# schematic.net
KiCad netlist of a schematic drawn in Altium Designer
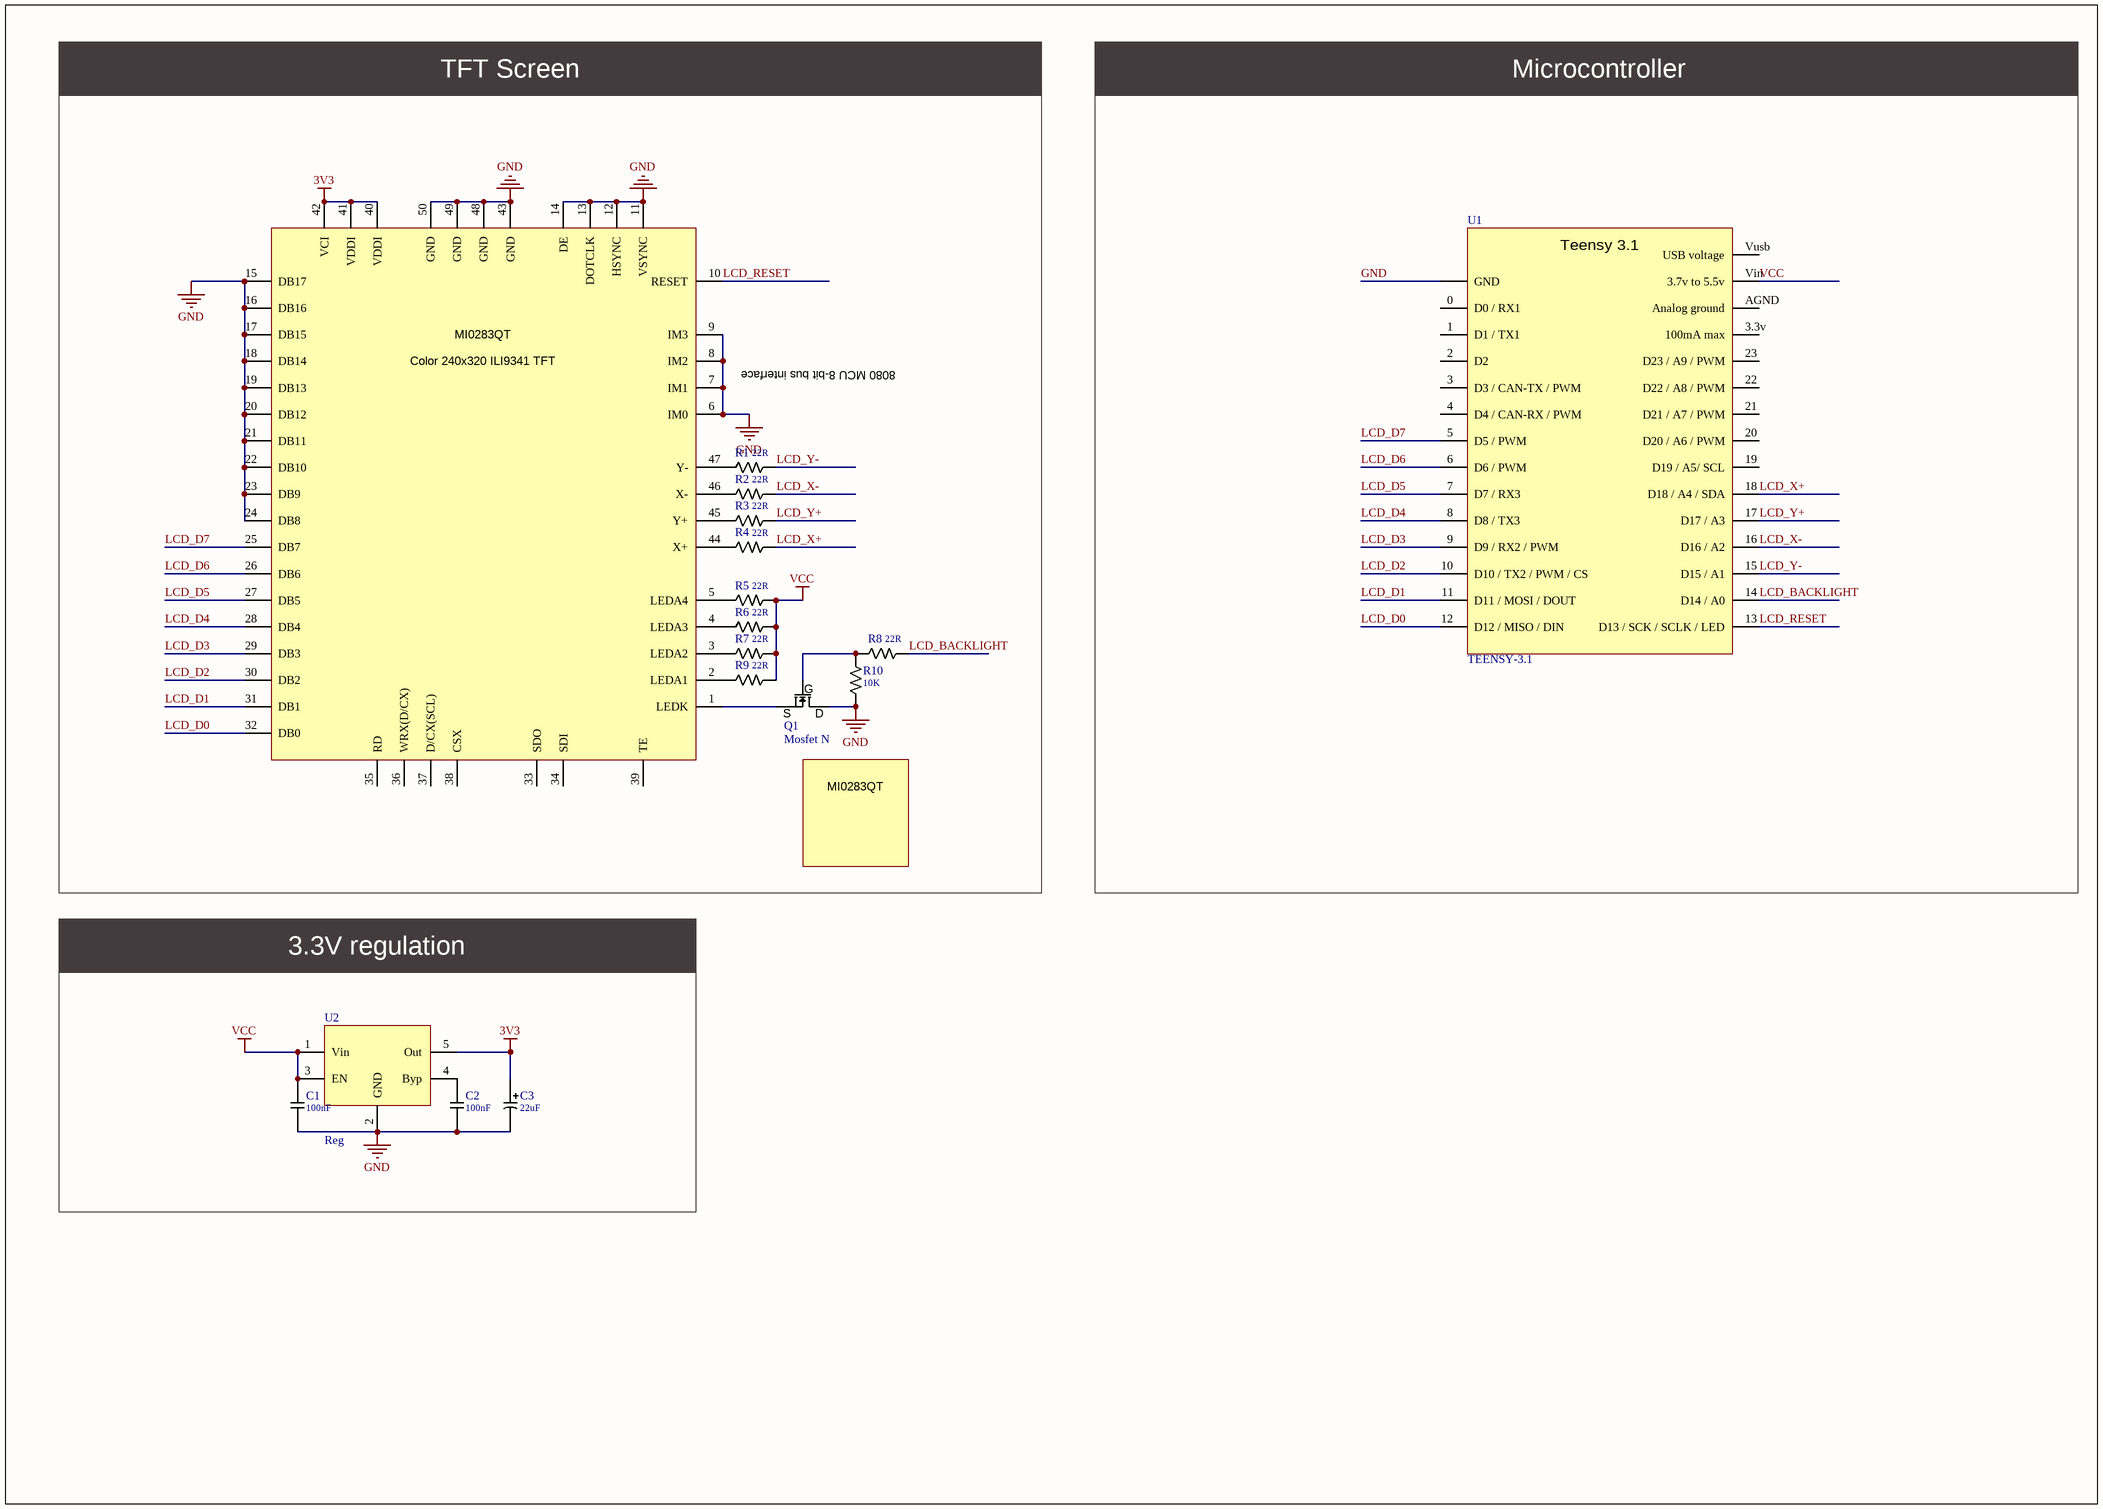
[diagram p0: schematic.SchDoc]

(export (version "E")
  (design (tool "Eeschema 10.0.6"))
  (components
    (comp (ref "C1")
      (value "100nF")
      (footprint "CAP-0603-GEN")
      (description "Capacitor")
      (fields (field (name "Comment") "CAPACITOR"))
      (libsource (lib "custom") (part "CAPACITOR"))
    )
    (comp (ref "C2")
      (value "100nF")
      (footprint "CAP-0603-GEN")
      (description "Capacitor")
      (fields (field (name "Comment") "CAPACITOR"))
      (libsource (lib "custom") (part "CAPACITOR"))
    )
    (comp (ref "C3")
      (value "22uF")
      (footprint "CAP-0603-POL")
      (description "Polarized capacitor")
      (fields (field (name "Comment") "CAPACITOR-POLARIZED"))
      (libsource (lib "custom") (part "CAPACITOR-POLARIZED"))
    )
    (comp (ref "Q1")
      (value "Mosfet N")
      (footprint "SOT23-3")
      (description "N-channel mosfet")
      (libsource (lib "custom") (part "MOSFET-N"))
    )
    (comp (ref "R1")
      (value "22R")
      (footprint "RESISTOR-0603")
      (description "Resistor")
      (fields (field (name "Comment") "RESISTOR"))
      (libsource (lib "custom") (part "RESISTOR"))
    )
    (comp (ref "R2")
      (value "22R")
      (footprint "RESISTOR-0603")
      (description "Resistor")
      (fields (field (name "Comment") "RESISTOR"))
      (libsource (lib "custom") (part "RESISTOR"))
    )
    (comp (ref "R3")
      (value "22R")
      (footprint "RESISTOR-0603")
      (description "Resistor")
      (fields (field (name "Comment") "RESISTOR"))
      (libsource (lib "custom") (part "RESISTOR"))
    )
    (comp (ref "R4")
      (value "22R")
      (footprint "RESISTOR-0603")
      (description "Resistor")
      (fields (field (name "Comment") "RESISTOR"))
      (libsource (lib "custom") (part "RESISTOR"))
    )
    (comp (ref "R5")
      (value "22R")
      (footprint "RESISTOR-0603")
      (description "Resistor")
      (fields (field (name "Comment") "RESISTOR"))
      (libsource (lib "custom") (part "RESISTOR"))
    )
    (comp (ref "R6")
      (value "22R")
      (footprint "RESISTOR-0603")
      (description "Resistor")
      (fields (field (name "Comment") "RESISTOR"))
      (libsource (lib "custom") (part "RESISTOR"))
    )
    (comp (ref "R7")
      (value "22R")
      (footprint "RESISTOR-0603")
      (description "Resistor")
      (fields (field (name "Comment") "RESISTOR"))
      (libsource (lib "custom") (part "RESISTOR"))
    )
    (comp (ref "R8")
      (value "22R")
      (footprint "RESISTOR-0603")
      (description "Resistor")
      (fields (field (name "Comment") "RESISTOR"))
      (libsource (lib "custom") (part "RESISTOR"))
    )
    (comp (ref "R9")
      (value "22R")
      (footprint "RESISTOR-0603")
      (description "Resistor")
      (fields (field (name "Comment") "RESISTOR"))
      (libsource (lib "custom") (part "RESISTOR"))
    )
    (comp (ref "R10")
      (value "10K")
      (footprint "RESISTOR-0603")
      (description "Resistor")
      (libsource (lib "custom") (part "RESISTOR"))
    )
    (comp (ref "TFT1")
      (value "TFT")
      (footprint "FCI-62684-50210E9ALF")
      (description "MI0283QT 2.8\" TFT")
      (libsource (lib "custom") (part "MI0283QT-11"))
    )
    (comp (ref "TFT2")
      (value "Screen")
      (footprint "MI0283QT")
      (description "MI0283QT TFT screen")
      (libsource (lib "custom") (part "MI0283QT"))
    )
    (comp (ref "U1")
      (value "TEENSY-3.1")
      (footprint "TEENSY-3.1")
      (description "Teensy 3.1 breakout")
      (libsource (lib "custom") (part "TEENSY-3.1"))
    )
    (comp (ref "U2")
      (value "Reg")
      (footprint "SOT23-5")
      (description "Voltage regulator")
      (libsource (lib "custom") (part "SOT23-REG"))
    )
  )
  (nets
    (net (code "1") (name "/LCD_BACKLIGHT") (class "Default")
      (node (ref "R8") (pin "2") (pinfunction "2_2") (pintype "passive"))
      (node (ref "U1") (pin "14") (pinfunction "D14_/_A0_14") (pintype "passive"))
    )
    (net (code "2") (name "/LCD_D0") (class "Default")
      (node (ref "TFT1") (pin "32") (pinfunction "DB0_32") (pintype "passive"))
      (node (ref "U1") (pin "12") (pinfunction "D12_/_MISO_/_DIN_12") (pintype "passive"))
    )
    (net (code "3") (name "/LCD_D1") (class "Default")
      (node (ref "TFT1") (pin "31") (pinfunction "DB1_31") (pintype "passive"))
      (node (ref "U1") (pin "11") (pinfunction "D11_/_MOSI_/_DOUT_11") (pintype "passive"))
    )
    (net (code "4") (name "/LCD_D2") (class "Default")
      (node (ref "TFT1") (pin "30") (pinfunction "DB2_30") (pintype "passive"))
      (node (ref "U1") (pin "10") (pinfunction "D10_/_TX2_/_PWM_/_CS_10") (pintype "passive"))
    )
    (net (code "5") (name "/LCD_D3") (class "Default")
      (node (ref "TFT1") (pin "29") (pinfunction "DB3_29") (pintype "passive"))
      (node (ref "U1") (pin "9") (pinfunction "D9_/_RX2_/_PWM_9") (pintype "passive"))
    )
    (net (code "6") (name "/LCD_D4") (class "Default")
      (node (ref "TFT1") (pin "28") (pinfunction "DB4_28") (pintype "passive"))
      (node (ref "U1") (pin "8") (pinfunction "D8_/_TX3_8") (pintype "passive"))
    )
    (net (code "7") (name "/LCD_D5") (class "Default")
      (node (ref "TFT1") (pin "27") (pinfunction "DB5_27") (pintype "passive"))
      (node (ref "U1") (pin "7") (pinfunction "D7_/_RX3_7") (pintype "passive"))
    )
    (net (code "8") (name "/LCD_D6") (class "Default")
      (node (ref "TFT1") (pin "26") (pinfunction "DB6_26") (pintype "passive"))
      (node (ref "U1") (pin "6") (pinfunction "D6_/_PWM_6") (pintype "passive"))
    )
    (net (code "9") (name "/LCD_D7") (class "Default")
      (node (ref "TFT1") (pin "25") (pinfunction "DB7_25") (pintype "passive"))
      (node (ref "U1") (pin "5") (pinfunction "D5_/_PWM_5") (pintype "passive"))
    )
    (net (code "10") (name "/LCD_RESET") (class "Default")
      (node (ref "TFT1") (pin "10") (pinfunction "RESET_10") (pintype "passive"))
      (node (ref "U1") (pin "13") (pinfunction "D13_/_SCK_/_SCLK_/_LED_13") (pintype "passive"))
    )
    (net (code "11") (name "/LCD_X+") (class "Default")
      (node (ref "R4") (pin "2") (pinfunction "2_2") (pintype "passive"))
      (node (ref "U1") (pin "18") (pinfunction "D18_/_A4_/_SDA_18") (pintype "passive"))
    )
    (net (code "12") (name "/LCD_X-") (class "Default")
      (node (ref "R2") (pin "2") (pinfunction "2_2") (pintype "passive"))
      (node (ref "U1") (pin "16") (pinfunction "D16_/_A2_16") (pintype "passive"))
    )
    (net (code "13") (name "/LCD_Y+") (class "Default")
      (node (ref "R3") (pin "2") (pinfunction "2_2") (pintype "passive"))
      (node (ref "U1") (pin "17") (pinfunction "D17_/_A3_17") (pintype "passive"))
    )
    (net (code "14") (name "/LCD_Y-") (class "Default")
      (node (ref "R1") (pin "2") (pinfunction "2_2") (pintype "passive"))
      (node (ref "U1") (pin "15") (pinfunction "D15_/_A1_15") (pintype "passive"))
    )
    (net (code "15") (name "3V3") (class "Default")
      (node (ref "C3") (pin "1") (pinfunction "1_1") (pintype "passive"))
      (node (ref "TFT1") (pin "40") (pinfunction "VDDI_40") (pintype "passive"))
      (node (ref "TFT1") (pin "41") (pinfunction "VDDI_41") (pintype "passive"))
      (node (ref "TFT1") (pin "42") (pinfunction "VCI_42") (pintype "passive"))
      (node (ref "U2") (pin "5") (pinfunction "Out_5") (pintype "passive"))
    )
    (net (code "16") (name "GND") (class "Default")
      (node (ref "C1") (pin "1") (pinfunction "1_1") (pintype "passive"))
      (node (ref "C2") (pin "1") (pinfunction "1_1") (pintype "passive"))
      (node (ref "C3") (pin "2") (pinfunction "2_2") (pintype "passive"))
      (node (ref "Q1") (pin "3") (pinfunction "Drain_3") (pintype "passive"))
      (node (ref "R10") (pin "2") (pinfunction "2_2") (pintype "passive"))
      (node (ref "TFT1") (pin "11") (pinfunction "VSYNC_11") (pintype "passive"))
      (node (ref "TFT1") (pin "12") (pinfunction "HSYNC_12") (pintype "passive"))
      (node (ref "TFT1") (pin "13") (pinfunction "DOTCLK_13") (pintype "passive"))
      (node (ref "TFT1") (pin "14") (pinfunction "DE_14") (pintype "passive"))
      (node (ref "TFT1") (pin "15") (pinfunction "DB17_15") (pintype "passive"))
      (node (ref "TFT1") (pin "16") (pinfunction "DB16_16") (pintype "passive"))
      (node (ref "TFT1") (pin "17") (pinfunction "DB15_17") (pintype "passive"))
      (node (ref "TFT1") (pin "18") (pinfunction "DB14_18") (pintype "passive"))
      (node (ref "TFT1") (pin "19") (pinfunction "DB13_19") (pintype "passive"))
      (node (ref "TFT1") (pin "20") (pinfunction "DB12_20") (pintype "passive"))
      (node (ref "TFT1") (pin "21") (pinfunction "DB11_21") (pintype "passive"))
      (node (ref "TFT1") (pin "22") (pinfunction "DB10_22") (pintype "passive"))
      (node (ref "TFT1") (pin "23") (pinfunction "DB9_23") (pintype "passive"))
      (node (ref "TFT1") (pin "24") (pinfunction "DB8_24") (pintype "passive"))
      (node (ref "TFT1") (pin "43") (pinfunction "GND_43") (pintype "passive"))
      (node (ref "TFT1") (pin "48") (pinfunction "GND_48") (pintype "passive"))
      (node (ref "TFT1") (pin "49") (pinfunction "GND_49") (pintype "passive"))
      (node (ref "TFT1") (pin "50") (pinfunction "GND_50") (pintype "passive"))
      (node (ref "TFT1") (pin "6") (pinfunction "IM0_6") (pintype "passive"))
      (node (ref "TFT1") (pin "7") (pinfunction "IM1_7") (pintype "passive"))
      (node (ref "TFT1") (pin "8") (pinfunction "IM2_8") (pintype "passive"))
      (node (ref "TFT1") (pin "9") (pinfunction "IM3_9") (pintype "passive"))
      (node (ref "U1") (pin "GND") (pinfunction "GND_GND") (pintype "passive"))
      (node (ref "U2") (pin "2") (pinfunction "GND_2") (pintype "passive"))
    )
    (net (code "17") (name "Net-(Q1-Gate)") (class "Default")
      (node (ref "Q1") (pin "1") (pinfunction "Gate_1") (pintype "passive"))
      (node (ref "R10") (pin "1") (pinfunction "1_1") (pintype "passive"))
      (node (ref "R8") (pin "1") (pinfunction "1_1") (pintype "passive"))
    )
    (net (code "18") (name "Net-(Q1-Source)") (class "Default")
      (node (ref "Q1") (pin "2") (pinfunction "Source_2") (pintype "passive"))
      (node (ref "TFT1") (pin "1") (pinfunction "LEDK_1") (pintype "passive"))
    )
    (net (code "19") (name "Net-(TFT1-LEDA1)") (class "Default")
      (node (ref "R9") (pin "1") (pinfunction "1_1") (pintype "passive"))
      (node (ref "TFT1") (pin "2") (pinfunction "LEDA1_2") (pintype "passive"))
    )
    (net (code "20") (name "Net-(TFT1-LEDA2)") (class "Default")
      (node (ref "R7") (pin "1") (pinfunction "1_1") (pintype "passive"))
      (node (ref "TFT1") (pin "3") (pinfunction "LEDA2_3") (pintype "passive"))
    )
    (net (code "21") (name "Net-(TFT1-LEDA3)") (class "Default")
      (node (ref "R6") (pin "1") (pinfunction "1_1") (pintype "passive"))
      (node (ref "TFT1") (pin "4") (pinfunction "LEDA3_4") (pintype "passive"))
    )
    (net (code "22") (name "Net-(TFT1-LEDA4)") (class "Default")
      (node (ref "R5") (pin "1") (pinfunction "1_1") (pintype "passive"))
      (node (ref "TFT1") (pin "5") (pinfunction "LEDA4_5") (pintype "passive"))
    )
    (net (code "23") (name "Net-(TFT1-X+)") (class "Default")
      (node (ref "R4") (pin "1") (pinfunction "1_1") (pintype "passive"))
      (node (ref "TFT1") (pin "44") (pinfunction "X+_44") (pintype "passive"))
    )
    (net (code "24") (name "Net-(TFT1-X-)") (class "Default")
      (node (ref "R2") (pin "1") (pinfunction "1_1") (pintype "passive"))
      (node (ref "TFT1") (pin "46") (pinfunction "X-_46") (pintype "passive"))
    )
    (net (code "25") (name "Net-(TFT1-Y+)") (class "Default")
      (node (ref "R3") (pin "1") (pinfunction "1_1") (pintype "passive"))
      (node (ref "TFT1") (pin "45") (pinfunction "Y+_45") (pintype "passive"))
    )
    (net (code "26") (name "Net-(TFT1-Y-)") (class "Default")
      (node (ref "R1") (pin "1") (pinfunction "1_1") (pintype "passive"))
      (node (ref "TFT1") (pin "47") (pinfunction "Y-_47") (pintype "passive"))
    )
    (net (code "27") (name "Net-(U2-Byp)") (class "Default")
      (node (ref "C2") (pin "2") (pinfunction "2_2") (pintype "passive"))
      (node (ref "U2") (pin "4") (pinfunction "Byp_4") (pintype "passive"))
    )
    (net (code "28") (name "VCC") (class "Default")
      (node (ref "C1") (pin "2") (pinfunction "2_2") (pintype "passive"))
      (node (ref "R5") (pin "2") (pinfunction "2_2") (pintype "passive"))
      (node (ref "R6") (pin "2") (pinfunction "2_2") (pintype "passive"))
      (node (ref "R7") (pin "2") (pinfunction "2_2") (pintype "passive"))
      (node (ref "R9") (pin "2") (pinfunction "2_2") (pintype "passive"))
      (node (ref "U1") (pin "Vin") (pinfunction "3.7v_to_5.5v_Vin") (pintype "passive"))
      (node (ref "U2") (pin "1") (pinfunction "Vin_1") (pintype "passive"))
      (node (ref "U2") (pin "3") (pinfunction "EN_3") (pintype "passive"))
    )
    (net (code "29") (name "unconnected-(TFT1-CSX-Pad38)") (class "Default")
      (node (ref "TFT1") (pin "38") (pinfunction "CSX_38") (pintype "passive"))
    )
    (net (code "30") (name "unconnected-(TFT1-D{slash}CX(SCL)-Pad37)") (class "Default")
      (node (ref "TFT1") (pin "37") (pinfunction "D/CX(SCL)_37") (pintype "passive"))
    )
    (net (code "31") (name "unconnected-(TFT1-RD-Pad35)") (class "Default")
      (node (ref "TFT1") (pin "35") (pinfunction "RD_35") (pintype "passive"))
    )
    (net (code "32") (name "unconnected-(TFT1-SDI-Pad34)") (class "Default")
      (node (ref "TFT1") (pin "34") (pinfunction "SDI_34") (pintype "passive"))
    )
    (net (code "33") (name "unconnected-(TFT1-SDO-Pad33)") (class "Default")
      (node (ref "TFT1") (pin "33") (pinfunction "SDO_33") (pintype "passive"))
    )
    (net (code "34") (name "unconnected-(TFT1-TE-Pad39)") (class "Default")
      (node (ref "TFT1") (pin "39") (pinfunction "TE_39") (pintype "passive"))
    )
    (net (code "35") (name "unconnected-(TFT1-WRX(D{slash}CX)-Pad36)") (class "Default")
      (node (ref "TFT1") (pin "36") (pinfunction "WRX(D/CX)_36") (pintype "passive"))
    )
    (net (code "36") (name "unconnected-(U1-100mA_max-Pad3.3v)") (class "Default")
      (node (ref "U1") (pin "3.3v") (pinfunction "100mA_max_3.3v") (pintype "passive"))
    )
    (net (code "37") (name "unconnected-(U1-Analog_ground-PadAGND)") (class "Default")
      (node (ref "U1") (pin "AGND") (pinfunction "Analog_ground_AGND") (pintype "passive"))
    )
    (net (code "38") (name "unconnected-(U1-D0_{slash}_RX1-Pad0)") (class "Default")
      (node (ref "U1") (pin "0") (pinfunction "D0_/_RX1_0") (pintype "passive"))
    )
    (net (code "39") (name "unconnected-(U1-D1_{slash}_TX1-Pad1)") (class "Default")
      (node (ref "U1") (pin "1") (pinfunction "D1_/_TX1_1") (pintype "passive"))
    )
    (net (code "40") (name "unconnected-(U1-D2-Pad2)") (class "Default")
      (node (ref "U1") (pin "2") (pinfunction "D2_2") (pintype "passive"))
    )
    (net (code "41") (name "unconnected-(U1-D3_{slash}_CAN-TX_{slash}_PWM-Pad3)") (class "Default")
      (node (ref "U1") (pin "3") (pinfunction "D3_/_CAN-TX_/_PWM_3") (pintype "passive"))
    )
    (net (code "42") (name "unconnected-(U1-D4_{slash}_CAN-RX_{slash}_PWM-Pad4)") (class "Default")
      (node (ref "U1") (pin "4") (pinfunction "D4_/_CAN-RX_/_PWM_4") (pintype "passive"))
    )
    (net (code "43") (name "unconnected-(U1-D19_{slash}_A5{slash}_SCL-Pad19)") (class "Default")
      (node (ref "U1") (pin "19") (pinfunction "D19_/_A5/_SCL_19") (pintype "passive"))
    )
    (net (code "44") (name "unconnected-(U1-D20_{slash}_A6_{slash}_PWM-Pad20)") (class "Default")
      (node (ref "U1") (pin "20") (pinfunction "D20_/_A6_/_PWM_20") (pintype "passive"))
    )
    (net (code "45") (name "unconnected-(U1-D21_{slash}_A7_{slash}_PWM-Pad21)") (class "Default")
      (node (ref "U1") (pin "21") (pinfunction "D21_/_A7_/_PWM_21") (pintype "passive"))
    )
    (net (code "46") (name "unconnected-(U1-D22_{slash}_A8_{slash}_PWM-Pad22)") (class "Default")
      (node (ref "U1") (pin "22") (pinfunction "D22_/_A8_/_PWM_22") (pintype "passive"))
    )
    (net (code "47") (name "unconnected-(U1-D23_{slash}_A9_{slash}_PWM-Pad23)") (class "Default")
      (node (ref "U1") (pin "23") (pinfunction "D23_/_A9_/_PWM_23") (pintype "passive"))
    )
    (net (code "48") (name "unconnected-(U1-USB_voltage-PadVusb)") (class "Default")
      (node (ref "U1") (pin "Vusb") (pinfunction "USB_voltage_Vusb") (pintype "passive"))
    )
  )
)
